# controller_rev4_2b.net
KiCad netlist of a schematic drawn in EAGLE
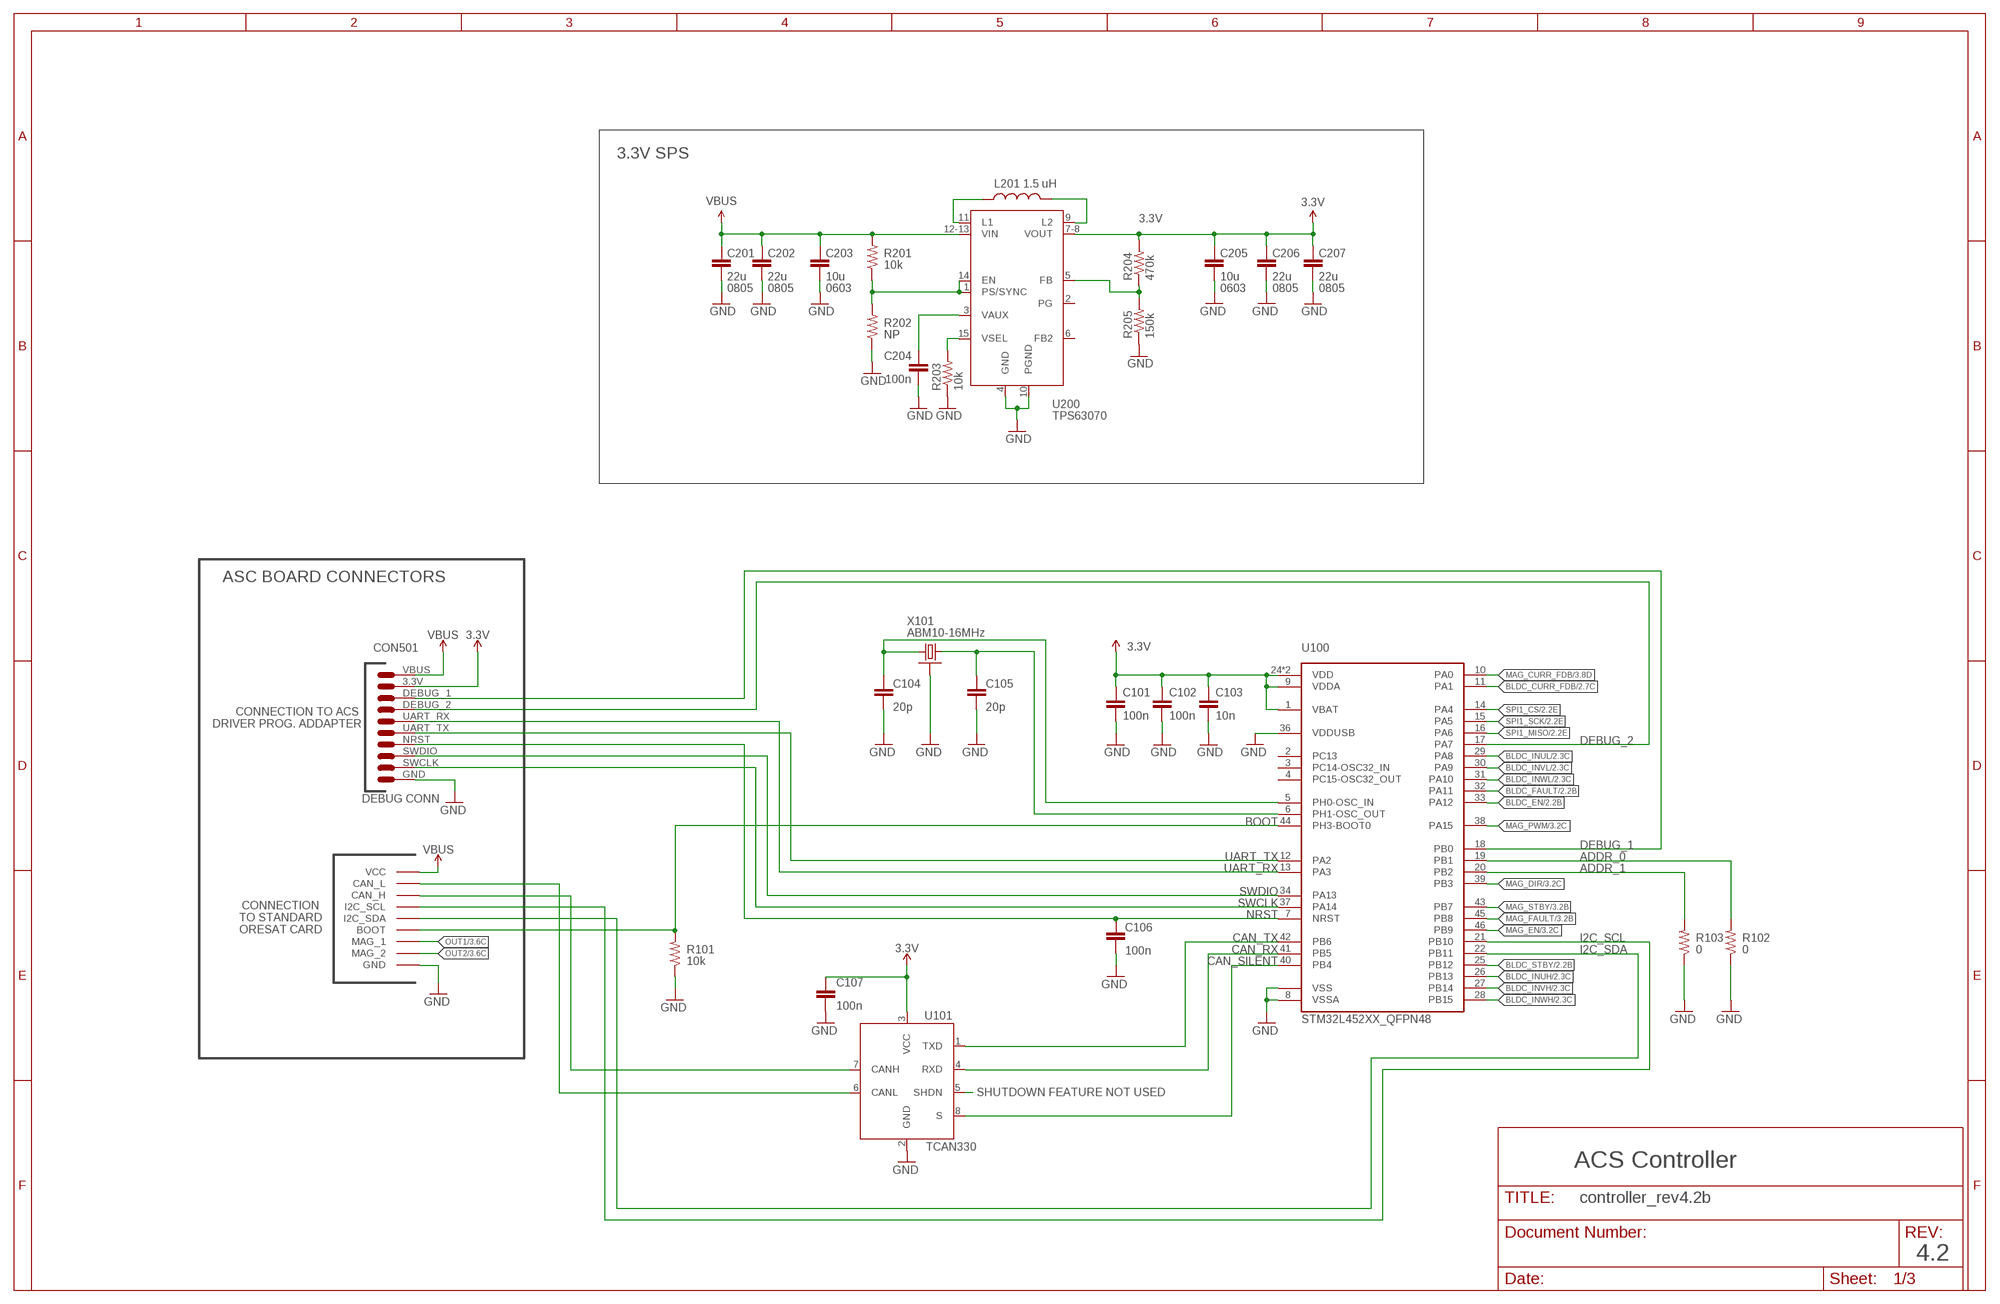
[diagram p0: schematic, sheet 1]
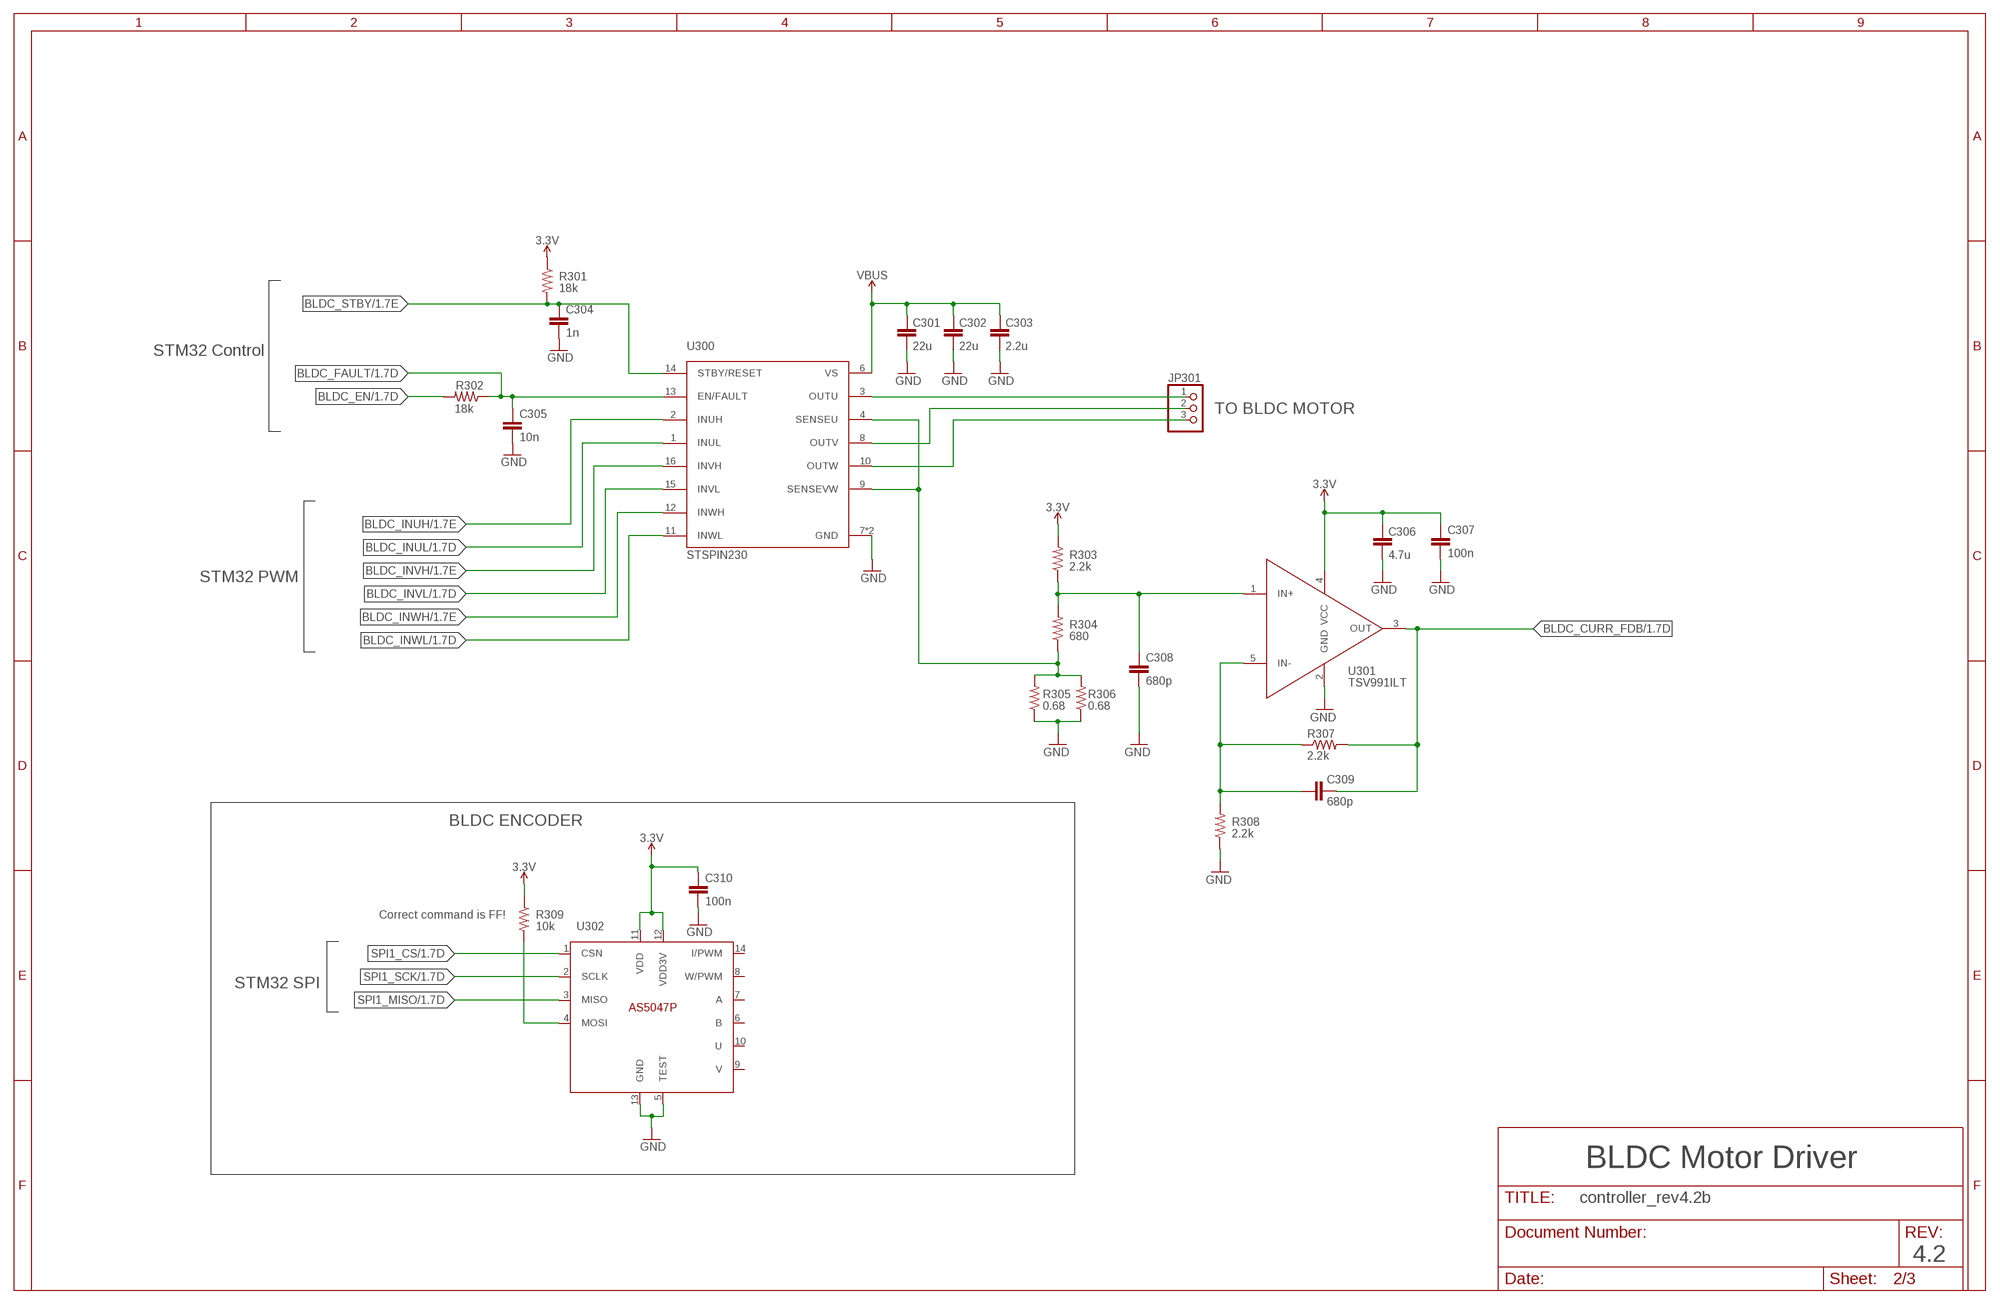
[diagram p1: schematic, sheet 2]
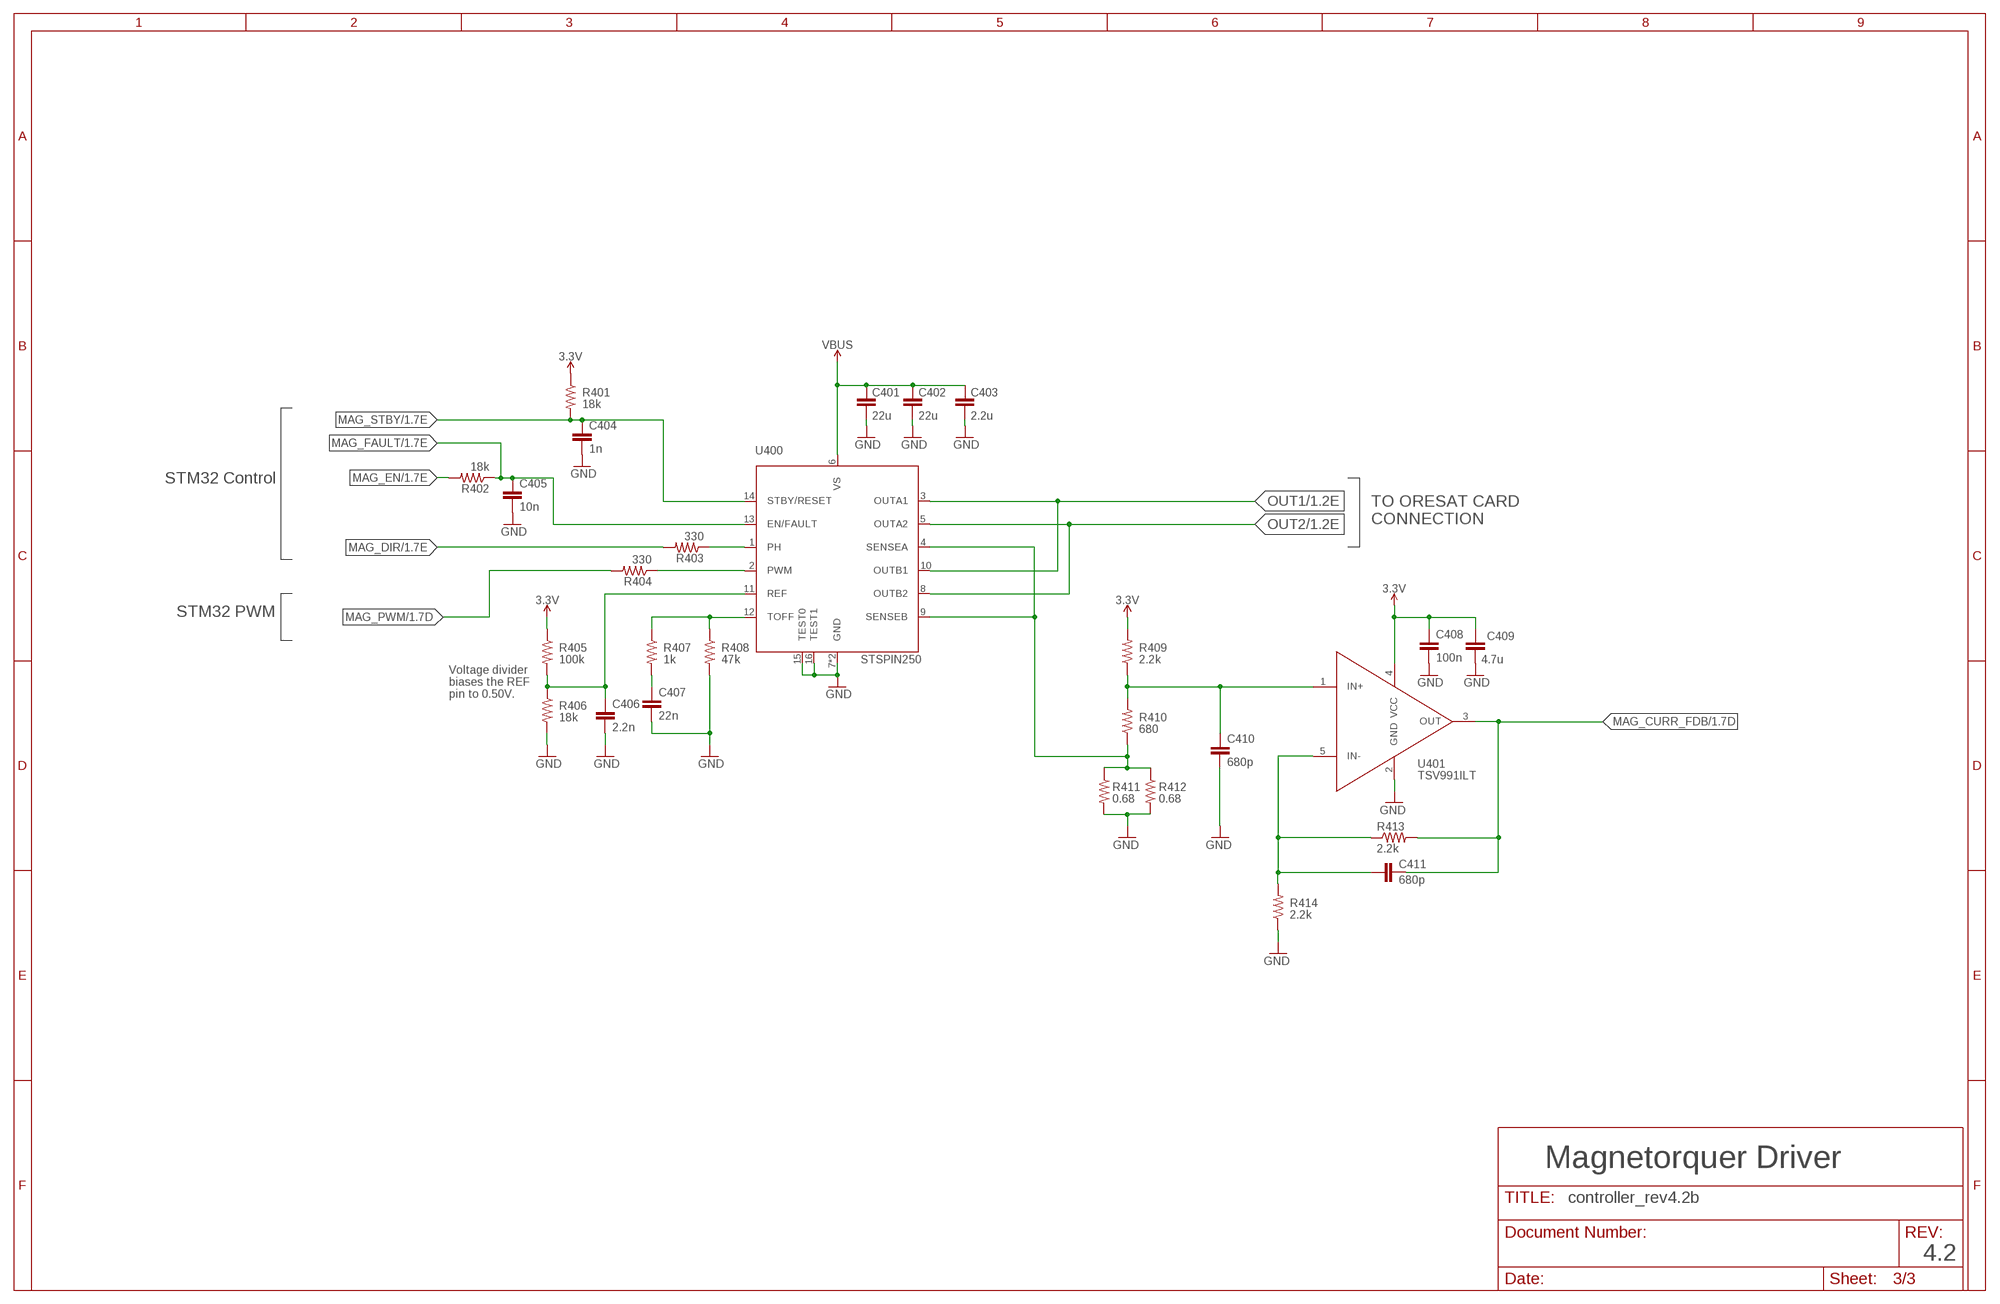
[diagram p2: schematic, sheet 3]

(export (version "E")
  (design (tool "Eeschema 10.0.6"))
  (components
    (comp (ref "C401")
      (value "22u")
      (footprint "eagle-import:.0603-B-NOSILK")
      (fields (field (name "MFR") "Samsung") (field (name "MPN") "CL05B104KO5NNNC"))
      (libsource (lib "eagle-import") (part "C-EU0603-B-NOSILK"))
    )
    (comp (ref "C402")
      (value "22u")
      (footprint "eagle-import:.0603-B-NOSILK")
      (fields (field (name "MFR") "Samsung") (field (name "MPN") "CL05B104KO5NNNC"))
      (libsource (lib "eagle-import") (part "C-EU0603-B-NOSILK"))
    )
    (comp (ref "C403")
      (value "2.2u")
      (footprint "eagle-import:.0603-B-NOSILK")
      (fields (field (name "MFR") "Samsung") (field (name "MPN") "CL05B104KO5NNNC"))
      (libsource (lib "eagle-import") (part "C-EU0603-B-NOSILK"))
    )
    (comp (ref "C404")
      (value "1n")
      (footprint "eagle-import:.0402-B-NOSILK")
      (fields (field (name "MFR") "Samsung") (field (name "MPN") "CL05B104KO5NNNC"))
      (libsource (lib "eagle-import") (part "rcl_custom_C-EU0402-B-NOSILK"))
    )
    (comp (ref "C405")
      (value "10n")
      (footprint "eagle-import:.0402-B-NOSILK")
      (fields (field (name "MFR") "Samsung") (field (name "MPN") "CL05B104KO5NNNC"))
      (libsource (lib "eagle-import") (part "rcl_custom_C-EU0402-B-NOSILK"))
    )
    (comp (ref "C406")
      (value "2.2n")
      (footprint "eagle-import:.0402-B-NOSILK")
      (fields (field (name "MFR") "Samsung") (field (name "MPN") "CL05B104KO5NNNC"))
      (libsource (lib "eagle-import") (part "rcl_custom_C-EU0402-B-NOSILK"))
    )
    (comp (ref "C407")
      (value "22n")
      (footprint "eagle-import:.0402-B-NOSILK")
      (fields (field (name "MFR") "Samsung") (field (name "MPN") "CL05B104KO5NNNC"))
      (libsource (lib "eagle-import") (part "rcl_custom_C-EU0402-B-NOSILK"))
    )
    (comp (ref "C408")
      (value "100n")
      (footprint "eagle-import:.0402-B-NOSILK")
      (fields (field (name "MFR") "Samsung") (field (name "MPN") "CL05B104KO5NNNC"))
      (libsource (lib "eagle-import") (part "rcl_custom_C-EU0402-B-NOSILK"))
    )
    (comp (ref "C409")
      (value "4.7u")
      (footprint "eagle-import:.0603-B-NOSILK")
      (fields (field (name "MFR") "Samsung") (field (name "MPN") "CL05B104KO5NNNC"))
      (libsource (lib "eagle-import") (part "C-EU0603-B-NOSILK"))
    )
    (comp (ref "C410")
      (value "680p")
      (footprint "eagle-import:.0402-B-NOSILK")
      (fields (field (name "MFR") "Samsung") (field (name "MPN") "CL05B104KO5NNNC"))
      (libsource (lib "eagle-import") (part "rcl_custom_C-EU0402-B-NOSILK"))
    )
    (comp (ref "C411")
      (value "680p")
      (footprint "eagle-import:.0402-B-NOSILK")
      (fields (field (name "MFR") "Samsung") (field (name "MPN") "CL05B104KO5NNNC"))
      (libsource (lib "eagle-import") (part "rcl_custom_C-EU0402-B-NOSILK"))
    )
    (comp (ref "R401")
      (value "18k")
      (footprint "eagle-import:.0402-B-NOSILK")
      (fields (field (name "MFR") "Samsung") (field (name "MPN") "RC1005F6653CS"))
      (libsource (lib "eagle-import") (part "rcl_custom_R-US_0402-B-NOSILK"))
    )
    (comp (ref "R402")
      (value "18k")
      (footprint "eagle-import:.0402-B-NOSILK")
      (fields (field (name "MFR") "Samsung") (field (name "MPN") "RC1005F6653CS"))
      (libsource (lib "eagle-import") (part "rcl_custom_R-US_0402-B-NOSILK"))
    )
    (comp (ref "R403")
      (value "330")
      (footprint "eagle-import:.0402-B-NOSILK")
      (fields (field (name "MFR") "Samsung") (field (name "MPN") "RC1005F6653CS"))
      (libsource (lib "eagle-import") (part "rcl_custom_R-US_0402-B-NOSILK"))
    )
    (comp (ref "R404")
      (value "330")
      (footprint "eagle-import:.0402-B-NOSILK")
      (fields (field (name "MFR") "Samsung") (field (name "MPN") "RC1005F6653CS"))
      (libsource (lib "eagle-import") (part "rcl_custom_R-US_0402-B-NOSILK"))
    )
    (comp (ref "R405")
      (value "100k")
      (footprint "eagle-import:.0402-B-NOSILK")
      (fields (field (name "MFR") "Samsung") (field (name "MPN") "RC1005F6653CS"))
      (libsource (lib "eagle-import") (part "rcl_custom_R-US_0402-B-NOSILK"))
    )
    (comp (ref "R406")
      (value "18k")
      (footprint "eagle-import:.0402-B-NOSILK")
      (fields (field (name "MFR") "Samsung") (field (name "MPN") "RC1005F6653CS"))
      (libsource (lib "eagle-import") (part "rcl_custom_R-US_0402-B-NOSILK"))
    )
    (comp (ref "R407")
      (value "1k")
      (footprint "eagle-import:.0402-B-NOSILK")
      (fields (field (name "MFR") "Samsung") (field (name "MPN") "RC1005F6653CS"))
      (libsource (lib "eagle-import") (part "rcl_custom_R-US_0402-B-NOSILK"))
    )
    (comp (ref "R408")
      (value "47k")
      (footprint "eagle-import:.0402-B-NOSILK")
      (fields (field (name "MFR") "Samsung") (field (name "MPN") "RC1005F6653CS"))
      (libsource (lib "eagle-import") (part "rcl_custom_R-US_0402-B-NOSILK"))
    )
    (comp (ref "R409")
      (value "2.2k")
      (footprint "eagle-import:.0402-B-NOSILK")
      (fields (field (name "MFR") "Samsung") (field (name "MPN") "RC1005F6653CS"))
      (libsource (lib "eagle-import") (part "rcl_custom_R-US_0402-B-NOSILK"))
    )
    (comp (ref "R410")
      (value "680")
      (footprint "eagle-import:.0402-B-NOSILK")
      (fields (field (name "MFR") "Samsung") (field (name "MPN") "RC1005F6653CS"))
      (libsource (lib "eagle-import") (part "rcl_custom_R-US_0402-B-NOSILK"))
    )
    (comp (ref "R411")
      (value "0.68")
      (footprint "eagle-import:.0805-B-NOSILK")
      (libsource (lib "eagle-import") (part "R-US_0805-B-NOSILK"))
    )
    (comp (ref "R412")
      (value "0.68")
      (footprint "eagle-import:.0805-B-NOSILK")
      (libsource (lib "eagle-import") (part "R-US_0805-B-NOSILK"))
    )
    (comp (ref "R413")
      (value "2.2k")
      (footprint "eagle-import:.0402-B-NOSILK")
      (fields (field (name "MFR") "Samsung") (field (name "MPN") "RC1005F6653CS"))
      (libsource (lib "eagle-import") (part "rcl_custom_R-US_0402-B-NOSILK"))
    )
    (comp (ref "R414")
      (value "2.2k")
      (footprint "eagle-import:.0402-B-NOSILK")
      (fields (field (name "MFR") "Samsung") (field (name "MPN") "RC1005F6653CS"))
      (libsource (lib "eagle-import") (part "rcl_custom_R-US_0402-B-NOSILK"))
    )
    (comp (ref "U400")
      (value "STSPIN250")
      (footprint "eagle-import:VFQPN")
      (libsource (lib "eagle-import") (part "STSPIN250"))
    )
    (comp (ref "U401")
      (value "TSV991ILT")
      (footprint "eagle-import:SOT23-5")
      (libsource (lib "eagle-import") (part "TSV991ILT"))
    )
    (comp (ref "C301")
      (value "22u")
      (footprint "eagle-import:.0603-B-NOSILK")
      (fields (field (name "MFR") "Samsung") (field (name "MPN") "CL05B104KO5NNNC"))
      (libsource (lib "eagle-import") (part "C-EU0603-B-NOSILK"))
    )
    (comp (ref "C302")
      (value "22u")
      (footprint "eagle-import:.0603-B-NOSILK")
      (fields (field (name "MFR") "Samsung") (field (name "MPN") "CL05B104KO5NNNC"))
      (libsource (lib "eagle-import") (part "C-EU0603-B-NOSILK"))
    )
    (comp (ref "C303")
      (value "2.2u")
      (footprint "eagle-import:.0603-B-NOSILK")
      (fields (field (name "MFR") "Samsung") (field (name "MPN") "CL05B104KO5NNNC"))
      (libsource (lib "eagle-import") (part "C-EU0603-B-NOSILK"))
    )
    (comp (ref "C304")
      (value "1n")
      (footprint "eagle-import:.0402-B-NOSILK")
      (fields (field (name "MFR") "Samsung") (field (name "MPN") "CL05B104KO5NNNC"))
      (libsource (lib "eagle-import") (part "rcl_custom_C-EU0402-B-NOSILK"))
    )
    (comp (ref "C305")
      (value "10n")
      (footprint "eagle-import:.0402-B-NOSILK")
      (fields (field (name "MFR") "Samsung") (field (name "MPN") "CL05B104KO5NNNC"))
      (libsource (lib "eagle-import") (part "rcl_custom_C-EU0402-B-NOSILK"))
    )
    (comp (ref "C306")
      (value "4.7u")
      (footprint "eagle-import:.0603-B-NOSILK")
      (fields (field (name "MFR") "Samsung") (field (name "MPN") "CL05B104KO5NNNC"))
      (libsource (lib "eagle-import") (part "C-EU0603-B-NOSILK"))
    )
    (comp (ref "C307")
      (value "100n")
      (footprint "eagle-import:.0402-B-NOSILK")
      (fields (field (name "MFR") "Samsung") (field (name "MPN") "CL05B104KO5NNNC"))
      (libsource (lib "eagle-import") (part "rcl_custom_C-EU0402-B-NOSILK"))
    )
    (comp (ref "C308")
      (value "680p")
      (footprint "eagle-import:.0402-B-NOSILK")
      (fields (field (name "MFR") "Samsung") (field (name "MPN") "CL05B104KO5NNNC"))
      (libsource (lib "eagle-import") (part "rcl_custom_C-EU0402-B-NOSILK"))
    )
    (comp (ref "C309")
      (value "680p")
      (footprint "eagle-import:.0402-B-NOSILK")
      (fields (field (name "MFR") "Samsung") (field (name "MPN") "CL05B104KO5NNNC"))
      (libsource (lib "eagle-import") (part "rcl_custom_C-EU0402-B-NOSILK"))
    )
    (comp (ref "C310")
      (value "100n")
      (footprint "eagle-import:.0402-B-NOSILK")
      (fields (field (name "MFR") "Samsung") (field (name "MPN") "CL05B104KO5NNNC"))
      (libsource (lib "eagle-import") (part "rcl_custom_C-EU0402-B-NOSILK"))
    )
    (comp (ref "JP301")
      (value "PINHD-1X03_2.00")
      (footprint "eagle-import:1X03M")
      (libsource (lib "eagle-import") (part "PINHD-1X03_2.00"))
    )
    (comp (ref "R301")
      (value "18k")
      (footprint "eagle-import:.0402-B-NOSILK")
      (fields (field (name "MFR") "Samsung") (field (name "MPN") "RC1005F6653CS"))
      (libsource (lib "eagle-import") (part "rcl_custom_R-US_0402-B-NOSILK"))
    )
    (comp (ref "R302")
      (value "18k")
      (footprint "eagle-import:.0402-B-NOSILK")
      (fields (field (name "MFR") "Samsung") (field (name "MPN") "RC1005F6653CS"))
      (libsource (lib "eagle-import") (part "rcl_custom_R-US_0402-B-NOSILK"))
    )
    (comp (ref "R303")
      (value "2.2k")
      (footprint "eagle-import:.0402-B-NOSILK")
      (fields (field (name "MFR") "Samsung") (field (name "MPN") "RC1005F6653CS"))
      (libsource (lib "eagle-import") (part "rcl_custom_R-US_0402-B-NOSILK"))
    )
    (comp (ref "R304")
      (value "680")
      (footprint "eagle-import:.0402-B-NOSILK")
      (fields (field (name "MFR") "Samsung") (field (name "MPN") "RC1005F6653CS"))
      (libsource (lib "eagle-import") (part "rcl_custom_R-US_0402-B-NOSILK"))
    )
    (comp (ref "R305")
      (value "0.68")
      (footprint "eagle-import:.0805-B-NOSILK")
      (libsource (lib "eagle-import") (part "R-US_0805-B-NOSILK"))
    )
    (comp (ref "R306")
      (value "0.68")
      (footprint "eagle-import:.0805-B-NOSILK")
      (libsource (lib "eagle-import") (part "R-US_0805-B-NOSILK"))
    )
    (comp (ref "R307")
      (value "2.2k")
      (footprint "eagle-import:.0402-B-NOSILK")
      (fields (field (name "MFR") "Samsung") (field (name "MPN") "RC1005F6653CS"))
      (libsource (lib "eagle-import") (part "rcl_custom_R-US_0402-B-NOSILK"))
    )
    (comp (ref "R308")
      (value "2.2k")
      (footprint "eagle-import:.0402-B-NOSILK")
      (fields (field (name "MFR") "Samsung") (field (name "MPN") "RC1005F6653CS"))
      (libsource (lib "eagle-import") (part "rcl_custom_R-US_0402-B-NOSILK"))
    )
    (comp (ref "R309")
      (value "10k")
      (footprint "eagle-import:.0402-B-NOSILK")
      (fields (field (name "MFR") "Samsung") (field (name "MPN") "RC1005F6653CS"))
      (libsource (lib "eagle-import") (part "rcl_custom_R-US_0402-B-NOSILK"))
    )
    (comp (ref "U300")
      (value "STSPIN230")
      (footprint "eagle-import:VFQPN")
      (libsource (lib "eagle-import") (part "STSPIN230"))
    )
    (comp (ref "U301")
      (value "TSV991ILT")
      (footprint "eagle-import:SOT23-5")
      (libsource (lib "eagle-import") (part "TSV991ILT"))
    )
    (comp (ref "U302")
      (value "AS5047P")
      (footprint "eagle-import:TSSOP14")
      (libsource (lib "eagle-import") (part "AS5047P"))
    )
    (comp (ref "C101")
      (value "100n")
      (footprint "eagle-import:.0402-B-NOSILK")
      (fields (field (name "MFR") "Samsung") (field (name "MPN") "CL05B104KO5NNNC"))
      (libsource (lib "eagle-import") (part "rcl_custom_C-EU0402-B-NOSILK"))
    )
    (comp (ref "C102")
      (value "100n")
      (footprint "eagle-import:.0402-B-NOSILK")
      (fields (field (name "MFR") "Samsung") (field (name "MPN") "CL05B104KO5NNNC"))
      (libsource (lib "eagle-import") (part "rcl_custom_C-EU0402-B-NOSILK"))
    )
    (comp (ref "C103")
      (value "10n")
      (footprint "eagle-import:.0402-B-NOSILK")
      (fields (field (name "MFR") "Samsung") (field (name "MPN") "CL05B104KO5NNNC"))
      (libsource (lib "eagle-import") (part "rcl_custom_C-EU0402-B-NOSILK"))
    )
    (comp (ref "C104")
      (value "20p")
      (footprint "eagle-import:.0402-B-NOSILK")
      (fields (field (name "MFR") "Samsung") (field (name "MPN") "CL05C200JB51PNC"))
      (libsource (lib "eagle-import") (part "rcl_custom_C-EU0402-B-NOSILK"))
    )
    (comp (ref "C105")
      (value "20p")
      (footprint "eagle-import:.0402-B-NOSILK")
      (fields (field (name "MFR") "Samsung") (field (name "MPN") "CL05C200JB51PNC"))
      (libsource (lib "eagle-import") (part "rcl_custom_C-EU0402-B-NOSILK"))
    )
    (comp (ref "C106")
      (value "100n")
      (footprint "eagle-import:.0402-B-NOSILK")
      (fields (field (name "MFR") "Samsung") (field (name "MPN") "CL05C200JB51PNC"))
      (libsource (lib "eagle-import") (part "rcl_custom_C-EU0402-B-NOSILK"))
    )
    (comp (ref "C107")
      (value "100n")
      (footprint "eagle-import:.0402-B-NOSILK")
      (fields (field (name "MFR") "Samsung") (field (name "MPN") "CL05B104KO5NNNC"))
      (libsource (lib "eagle-import") (part "rcl_custom_C-EU0402-B-NOSILK"))
    )
    (comp (ref "C201")
      (value "22u")
      (footprint "eagle-import:.0805-B-NOSILK")
      (libsource (lib "eagle-import") (part "C-EU0805-B-NOSILK"))
    )
    (comp (ref "C202")
      (value "22u")
      (footprint "eagle-import:.0805-B-NOSILK")
      (libsource (lib "eagle-import") (part "C-EU0805-B-NOSILK"))
    )
    (comp (ref "C203")
      (value "10u")
      (footprint "eagle-import:.0603-B-NOSILK")
      (fields (field (name "MFR") "Samsung") (field (name "MPN") "CL05B104KO5NNNC"))
      (libsource (lib "eagle-import") (part "C-EU0603-B-NOSILK"))
    )
    (comp (ref "C204")
      (value "100n")
      (footprint "eagle-import:.0402-B-NOSILK")
      (fields (field (name "MFR") "Samsung") (field (name "MPN") "CL05B104KO5NNNC"))
      (libsource (lib "eagle-import") (part "rcl_custom_C-EU0402-B-NOSILK"))
    )
    (comp (ref "C205")
      (value "10u")
      (footprint "eagle-import:.0603-B-NOSILK")
      (fields (field (name "MFR") "Samsung") (field (name "MPN") "CL05B104KO5NNNC"))
      (libsource (lib "eagle-import") (part "C-EU0603-B-NOSILK"))
    )
    (comp (ref "C206")
      (value "22u")
      (footprint "eagle-import:.0805-B-NOSILK")
      (libsource (lib "eagle-import") (part "C-EU0805-B-NOSILK"))
    )
    (comp (ref "C207")
      (value "22u")
      (footprint "eagle-import:.0805-B-NOSILK")
      (libsource (lib "eagle-import") (part "C-EU0805-B-NOSILK"))
    )
    (comp (ref "C501")
      (value "DEBUG_CON")
      (footprint "eagle-import:DEBUG_CON")
      (libsource (lib "eagle-import") (part "DEBUG_CON"))
    )
    (comp (ref "L201")
      (value "1.5 uH")
      (footprint "eagle-import:L-COILCRAFT-XFL4020")
      (fields (field (name "MFR") "Coilcraft") (field (name "MPN") "XFL4020-152ME"))
      (libsource (lib "eagle-import") (part "L-COILCRAFT-XFL4020"))
    )
    (comp (ref "R101")
      (value "10k")
      (footprint "eagle-import:.0402-B-NOSILK")
      (fields (field (name "MFR") "Samsung") (field (name "MPN") "RC1005F6653CS"))
      (libsource (lib "eagle-import") (part "rcl_custom_R-US_0402-B-NOSILK"))
    )
    (comp (ref "R102")
      (value "0")
      (footprint "eagle-import:.0402-B-NOSILK")
      (fields (field (name "MFR") "Samsung") (field (name "MPN") "RC1005F6653CS"))
      (libsource (lib "eagle-import") (part "rcl_custom_R-US_0402-B-NOSILK"))
    )
    (comp (ref "R103")
      (value "0")
      (footprint "eagle-import:.0402-B-NOSILK")
      (fields (field (name "MFR") "Samsung") (field (name "MPN") "RC1005F6653CS"))
      (libsource (lib "eagle-import") (part "rcl_custom_R-US_0402-B-NOSILK"))
    )
    (comp (ref "R201")
      (value "10k")
      (footprint "eagle-import:.0402-B-NOSILK")
      (fields (field (name "MFR") "Samsung") (field (name "MPN") "RC1005F6653CS"))
      (libsource (lib "eagle-import") (part "rcl_custom_R-US_0402-B-NOSILK"))
    )
    (comp (ref "R202")
      (value "NP")
      (footprint "eagle-import:.0402-B-NOSILK")
      (fields (field (name "MFR") "Samsung") (field (name "MPN") "RC1005F6653CS"))
      (libsource (lib "eagle-import") (part "rcl_custom_R-US_0402-B-NOSILK"))
    )
    (comp (ref "R203")
      (value "10k")
      (footprint "eagle-import:.0402-B-NOSILK")
      (fields (field (name "MFR") "Samsung") (field (name "MPN") "RC1005F6653CS"))
      (libsource (lib "eagle-import") (part "rcl_custom_R-US_0402-B-NOSILK"))
    )
    (comp (ref "R204")
      (value "470k")
      (footprint "eagle-import:.0402-B-NOSILK")
      (fields (field (name "MFR") "Samsung") (field (name "MPN") "RC1005F6653CS"))
      (libsource (lib "eagle-import") (part "rcl_custom_R-US_0402-B-NOSILK"))
    )
    (comp (ref "R205")
      (value "150k")
      (footprint "eagle-import:.0402-B-NOSILK")
      (fields (field (name "MFR") "Samsung") (field (name "MPN") "RC1005F6653CS"))
      (libsource (lib "eagle-import") (part "rcl_custom_R-US_0402-B-NOSILK"))
    )
    (comp (ref "U$2")
      (value "MEZZANINE_1")
      (footprint "eagle-import:MEZZANINE_1")
      (libsource (lib "eagle-import") (part "MEZZANINE_1"))
    )
    (comp (ref "U100")
      (value "STM32L452XX_QFPN48")
      (footprint "eagle-import:QFPN-48")
      (libsource (lib "eagle-import") (part "STM32L452XX_QFPN48"))
    )
    (comp (ref "U101")
      (value "TCAN330")
      (footprint "eagle-import:SOT23-8_TI-DCN")
      (fields (field (name "MFR") "Texas Instruments") (field (name "MPN") "TCAN330GDCNT"))
      (libsource (lib "eagle-import") (part "TCAN330"))
    )
    (comp (ref "U200")
      (value "TPS63070")
      (footprint "eagle-import:TPS63070X")
      (fields (field (name "MFR") "TI"))
      (libsource (lib "eagle-import") (part "TPS63070X"))
    )
    (comp (ref "X101")
      (value "ABM10-16MHz")
      (footprint "eagle-import:CRYSTAL_2.5X2")
      (fields (field (name "MFR") "ECS Inc.") (field (name "MPN") "ECS-160-10-36Q-ES-TR"))
      (libsource (lib "eagle-import") (part "CRYSTAL-WITH-GND"))
    )
  )
  (nets
    (net (code "1") (name "3.3V") (class "Default")
      (node (ref "C101") (pin "1") (pinfunction "1_1") (pintype "passive"))
      (node (ref "C102") (pin "1") (pinfunction "1_1") (pintype "passive"))
      (node (ref "C103") (pin "1") (pinfunction "1_1") (pintype "passive"))
      (node (ref "C107") (pin "1") (pinfunction "1_1") (pintype "passive"))
      (node (ref "C205") (pin "1") (pinfunction "1_1") (pintype "passive"))
      (node (ref "C206") (pin "1") (pinfunction "1_1") (pintype "passive"))
      (node (ref "C207") (pin "1") (pinfunction "1_1") (pintype "passive"))
      (node (ref "C306") (pin "1") (pinfunction "1_1") (pintype "passive"))
      (node (ref "C307") (pin "1") (pinfunction "1_1") (pintype "passive"))
      (node (ref "C310") (pin "1") (pinfunction "1_1") (pintype "passive"))
      (node (ref "C408") (pin "1") (pinfunction "1_1") (pintype "passive"))
      (node (ref "C409") (pin "1") (pinfunction "1_1") (pintype "passive"))
      (node (ref "C501") (pin "3.3V") (pinfunction "2_3.3V") (pintype "bidirectional"))
      (node (ref "R204") (pin "2") (pinfunction "2_2") (pintype "passive"))
      (node (ref "R301") (pin "1") (pinfunction "1_1") (pintype "passive"))
      (node (ref "R303") (pin "2") (pinfunction "2_2") (pintype "passive"))
      (node (ref "R309") (pin "1") (pinfunction "1_1") (pintype "passive"))
      (node (ref "R401") (pin "1") (pinfunction "1_1") (pintype "passive"))
      (node (ref "R405") (pin "1") (pinfunction "1_1") (pintype "passive"))
      (node (ref "R409") (pin "2") (pinfunction "2_2") (pintype "passive"))
      (node (ref "U100") (pin "1") (pinfunction "VBAT_1") (pintype "bidirectional"))
      (node (ref "U100") (pin "24") (pinfunction "VDD_24") (pintype "bidirectional"))
      (node (ref "U100") (pin "48") (pinfunction "VDD_48") (pintype "bidirectional"))
      (node (ref "U100") (pin "9") (pinfunction "VDDA_9") (pintype "bidirectional"))
      (node (ref "U101") (pin "3") (pinfunction "VCC_3") (pintype "power_in"))
      (node (ref "U200") (pin "7-8") (pinfunction "VOUT_7-8") (pintype "power_in"))
      (node (ref "U301") (pin "4") (pinfunction "VCC_4") (pintype "bidirectional"))
      (node (ref "U302") (pin "11") (pinfunction "VDD_11") (pintype "power_in"))
      (node (ref "U302") (pin "12") (pinfunction "VDD3V_12") (pintype "power_in"))
      (node (ref "U401") (pin "4") (pinfunction "VCC_4") (pintype "bidirectional"))
    )
    (net (code "2") (name "ADDR_0") (class "Default")
      (node (ref "R102") (pin "2") (pinfunction "2_2") (pintype "passive"))
      (node (ref "U100") (pin "19") (pinfunction "PB1_19") (pintype "bidirectional"))
    )
    (net (code "3") (name "ADDR_1") (class "Default")
      (node (ref "R103") (pin "2") (pinfunction "2_2") (pintype "passive"))
      (node (ref "U100") (pin "20") (pinfunction "PB2_20") (pintype "bidirectional"))
    )
    (net (code "4") (name "BLDC_CURR_FDB") (class "Default")
      (node (ref "C309") (pin "1") (pinfunction "1_1") (pintype "passive"))
      (node (ref "R307") (pin "2") (pinfunction "2_2") (pintype "passive"))
      (node (ref "U100") (pin "11") (pinfunction "PA1_11") (pintype "bidirectional"))
      (node (ref "U301") (pin "3") (pinfunction "OUT_3") (pintype "bidirectional"))
    )
    (net (code "5") (name "BLDC_EN") (class "Default")
      (node (ref "R302") (pin "2") (pinfunction "2_2") (pintype "passive"))
      (node (ref "U100") (pin "33") (pinfunction "PA12_33") (pintype "bidirectional"))
    )
    (net (code "6") (name "BLDC_FAULT") (class "Default")
      (node (ref "C305") (pin "1") (pinfunction "1_1") (pintype "passive"))
      (node (ref "R302") (pin "1") (pinfunction "1_1") (pintype "passive"))
      (node (ref "U100") (pin "32") (pinfunction "PA11_32") (pintype "bidirectional"))
      (node (ref "U300") (pin "13") (pinfunction "EN/FAULT_13") (pintype "bidirectional"))
    )
    (net (code "7") (name "BLDC_INUH") (class "Default")
      (node (ref "U100") (pin "26") (pinfunction "PB13_26") (pintype "bidirectional"))
      (node (ref "U300") (pin "2") (pinfunction "INUH_2") (pintype "input"))
    )
    (net (code "8") (name "BLDC_INUL") (class "Default")
      (node (ref "U100") (pin "29") (pinfunction "PA8_29") (pintype "bidirectional"))
      (node (ref "U300") (pin "1") (pinfunction "INUL_1") (pintype "input"))
    )
    (net (code "9") (name "BLDC_INVH") (class "Default")
      (node (ref "U100") (pin "27") (pinfunction "PB14_27") (pintype "bidirectional"))
      (node (ref "U300") (pin "16") (pinfunction "INVH_16") (pintype "input"))
    )
    (net (code "10") (name "BLDC_INVL") (class "Default")
      (node (ref "U100") (pin "30") (pinfunction "PA9_30") (pintype "bidirectional"))
      (node (ref "U300") (pin "15") (pinfunction "INVL_15") (pintype "input"))
    )
    (net (code "11") (name "BLDC_INWH") (class "Default")
      (node (ref "U100") (pin "28") (pinfunction "PB15_28") (pintype "bidirectional"))
      (node (ref "U300") (pin "12") (pinfunction "INWH_12") (pintype "input"))
    )
    (net (code "12") (name "BLDC_INWL") (class "Default")
      (node (ref "U100") (pin "31") (pinfunction "PA10_31") (pintype "bidirectional"))
      (node (ref "U300") (pin "11") (pinfunction "INWL_11") (pintype "input"))
    )
    (net (code "13") (name "BLDC_STBY") (class "Default")
      (node (ref "C304") (pin "1") (pinfunction "1_1") (pintype "passive"))
      (node (ref "R301") (pin "2") (pinfunction "2_2") (pintype "passive"))
      (node (ref "U100") (pin "25") (pinfunction "PB12_25") (pintype "bidirectional"))
      (node (ref "U300") (pin "14") (pinfunction "STBY/RESET_14") (pintype "input"))
    )
    (net (code "14") (name "BOOT") (class "Default")
      (node (ref "R101") (pin "2") (pinfunction "2_2") (pintype "passive"))
      (node (ref "U$2") (pin "P$22") (pinfunction "BOOT_P$22") (pintype "bidirectional"))
      (node (ref "U$2") (pin "P$9") (pinfunction "BOOT_P$9") (pintype "bidirectional"))
      (node (ref "U100") (pin "44") (pinfunction "PH3-BOOT0_44") (pintype "bidirectional"))
    )
    (net (code "15") (name "CAN_RX") (class "Default")
      (node (ref "U100") (pin "41") (pinfunction "PB5_41") (pintype "bidirectional"))
      (node (ref "U101") (pin "4") (pinfunction "RXD_4") (pintype "output"))
    )
    (net (code "16") (name "CAN_SILENT") (class "Default")
      (node (ref "U100") (pin "40") (pinfunction "PB4_40") (pintype "bidirectional"))
      (node (ref "U101") (pin "8") (pinfunction "S_8") (pintype "input"))
    )
    (net (code "17") (name "CAN_TX") (class "Default")
      (node (ref "U100") (pin "42") (pinfunction "PB6_42") (pintype "bidirectional"))
      (node (ref "U101") (pin "1") (pinfunction "TXD_1") (pintype "input"))
    )
    (net (code "18") (name "DEBUG_1") (class "Default")
      (node (ref "C501") (pin "DEBUG_1") (pinfunction "3_DEBUG_1") (pintype "bidirectional"))
      (node (ref "U100") (pin "18") (pinfunction "PB0_18") (pintype "bidirectional"))
    )
    (net (code "19") (name "DEBUG_2") (class "Default")
      (node (ref "C501") (pin "DEBUG_2") (pinfunction "4_DEBUG_2") (pintype "bidirectional"))
      (node (ref "U100") (pin "17") (pinfunction "PA7_17") (pintype "bidirectional"))
    )
    (net (code "20") (name "GND") (class "Default")
      (node (ref "C101") (pin "2") (pinfunction "2_2") (pintype "passive"))
      (node (ref "C102") (pin "2") (pinfunction "2_2") (pintype "passive"))
      (node (ref "C103") (pin "2") (pinfunction "2_2") (pintype "passive"))
      (node (ref "C104") (pin "2") (pinfunction "2_2") (pintype "passive"))
      (node (ref "C105") (pin "2") (pinfunction "2_2") (pintype "passive"))
      (node (ref "C106") (pin "2") (pinfunction "2_2") (pintype "passive"))
      (node (ref "C107") (pin "2") (pinfunction "2_2") (pintype "passive"))
      (node (ref "C201") (pin "2") (pinfunction "2_2") (pintype "passive"))
      (node (ref "C202") (pin "2") (pinfunction "2_2") (pintype "passive"))
      (node (ref "C203") (pin "2") (pinfunction "2_2") (pintype "passive"))
      (node (ref "C204") (pin "2") (pinfunction "2_2") (pintype "passive"))
      (node (ref "C205") (pin "2") (pinfunction "2_2") (pintype "passive"))
      (node (ref "C206") (pin "2") (pinfunction "2_2") (pintype "passive"))
      (node (ref "C207") (pin "2") (pinfunction "2_2") (pintype "passive"))
      (node (ref "C301") (pin "2") (pinfunction "2_2") (pintype "passive"))
      (node (ref "C302") (pin "2") (pinfunction "2_2") (pintype "passive"))
      (node (ref "C303") (pin "2") (pinfunction "2_2") (pintype "passive"))
      (node (ref "C304") (pin "2") (pinfunction "2_2") (pintype "passive"))
      (node (ref "C305") (pin "2") (pinfunction "2_2") (pintype "passive"))
      (node (ref "C306") (pin "2") (pinfunction "2_2") (pintype "passive"))
      (node (ref "C307") (pin "2") (pinfunction "2_2") (pintype "passive"))
      (node (ref "C308") (pin "2") (pinfunction "2_2") (pintype "passive"))
      (node (ref "C310") (pin "2") (pinfunction "2_2") (pintype "passive"))
      (node (ref "C401") (pin "2") (pinfunction "2_2") (pintype "passive"))
      (node (ref "C402") (pin "2") (pinfunction "2_2") (pintype "passive"))
      (node (ref "C403") (pin "2") (pinfunction "2_2") (pintype "passive"))
      (node (ref "C404") (pin "2") (pinfunction "2_2") (pintype "passive"))
      (node (ref "C405") (pin "2") (pinfunction "2_2") (pintype "passive"))
      (node (ref "C406") (pin "2") (pinfunction "2_2") (pintype "passive"))
      (node (ref "C407") (pin "2") (pinfunction "2_2") (pintype "passive"))
      (node (ref "C408") (pin "2") (pinfunction "2_2") (pintype "passive"))
      (node (ref "C409") (pin "2") (pinfunction "2_2") (pintype "passive"))
      (node (ref "C410") (pin "2") (pinfunction "2_2") (pintype "passive"))
      (node (ref "C501") (pin "GND") (pinfunction "10_GND") (pintype "bidirectional"))
      (node (ref "R101") (pin "1") (pinfunction "1_1") (pintype "passive"))
      (node (ref "R102") (pin "1") (pinfunction "1_1") (pintype "passive"))
      (node (ref "R103") (pin "1") (pinfunction "1_1") (pintype "passive"))
      (node (ref "R202") (pin "1") (pinfunction "1_1") (pintype "passive"))
      (node (ref "R203") (pin "1") (pinfunction "1_1") (pintype "passive"))
      (node (ref "R205") (pin "1") (pinfunction "1_1") (pintype "passive"))
      (node (ref "R305") (pin "1") (pinfunction "1_1") (pintype "passive"))
      (node (ref "R306") (pin "1") (pinfunction "1_1") (pintype "passive"))
      (node (ref "R308") (pin "1") (pinfunction "1_1") (pintype "passive"))
      (node (ref "R406") (pin "2") (pinfunction "2_2") (pintype "passive"))
      (node (ref "R408") (pin "2") (pinfunction "2_2") (pintype "passive"))
      (node (ref "R411") (pin "2") (pinfunction "2_2") (pintype "passive"))
      (node (ref "R412") (pin "2") (pinfunction "2_2") (pintype "passive"))
      (node (ref "R414") (pin "1") (pinfunction "1_1") (pintype "passive"))
      (node (ref "U$2") (pin "P$1") (pinfunction "GND_P$1") (pintype "bidirectional"))
      (node (ref "U$2") (pin "P$14") (pinfunction "GND_P$14") (pintype "bidirectional"))
      (node (ref "U$2") (pin "P$15") (pinfunction "GND_P$15") (pintype "bidirectional"))
      (node (ref "U$2") (pin "P$16") (pinfunction "GND_P$16") (pintype "bidirectional"))
      (node (ref "U$2") (pin "P$17") (pinfunction "GND_P$17") (pintype "bidirectional"))
      (node (ref "U$2") (pin "P$2") (pinfunction "GND_P$2") (pintype "bidirectional"))
      (node (ref "U$2") (pin "P$29") (pinfunction "GND_P$29") (pintype "bidirectional"))
      (node (ref "U$2") (pin "P$30") (pinfunction "GND_P$30") (pintype "bidirectional"))
      (node (ref "U100") (pin "23") (pinfunction "VSS_23") (pintype "bidirectional"))
      (node (ref "U100") (pin "35") (pinfunction "VSS_35") (pintype "bidirectional"))
      (node (ref "U100") (pin "36") (pinfunction "VDDUSB_36") (pintype "bidirectional"))
      (node (ref "U100") (pin "47") (pinfunction "VSS_47") (pintype "bidirectional"))
      (node (ref "U100") (pin "8") (pinfunction "VSSA_8") (pintype "bidirectional"))
      (node (ref "U100") (pin "EPAD") (pinfunction "VSS_EPAD") (pintype "bidirectional"))
      (node (ref "U101") (pin "2") (pinfunction "GND_2") (pintype "power_in"))
      (node (ref "U200") (pin "10") (pinfunction "PGND_10") (pintype "power_in"))
      (node (ref "U200") (pin "4") (pinfunction "GND_4") (pintype "power_in"))
      (node (ref "U300") (pin "7") (pinfunction "GND_7") (pintype "power_in"))
      (node (ref "U300") (pin "EPAD") (pinfunction "GND_EPAD") (pintype "power_in"))
      (node (ref "U301") (pin "2") (pinfunction "GND_2") (pintype "bidirectional"))
      (node (ref "U302") (pin "13") (pinfunction "GND_13") (pintype "power_in"))
      (node (ref "U302") (pin "5") (pinfunction "TEST_5") (pintype "power_in"))
      (node (ref "U400") (pin "15") (pinfunction "TEST0_15") (pintype "bidirectional"))
      (node (ref "U400") (pin "16") (pinfunction "TEST1_16") (pintype "bidirectional"))
      (node (ref "U400") (pin "7") (pinfunction "GND_7") (pintype "power_in"))
      (node (ref "U400") (pin "EPAD") (pinfunction "GND_EPAD") (pintype "power_in"))
      (node (ref "U401") (pin "2") (pinfunction "GND_2") (pintype "bidirectional"))
      (node (ref "X101") (pin "2") (pinfunction "SHIELD_2") (pintype "power_in"))
      (node (ref "X101") (pin "4") (pinfunction "SHIELD_4") (pintype "power_in"))
    )
    (net (code "21") (name "I2C_SCL") (class "Default")
      (node (ref "U$2") (pin "P$24") (pinfunction "I2C_SCL_P$24") (pintype "bidirectional"))
      (node (ref "U$2") (pin "P$7") (pinfunction "I2C_SCL_P$7") (pintype "bidirectional"))
      (node (ref "U100") (pin "21") (pinfunction "PB10_21") (pintype "bidirectional"))
    )
    (net (code "22") (name "I2C_SDA") (class "Default")
      (node (ref "U$2") (pin "P$23") (pinfunction "I2C_SDA_P$23") (pintype "bidirectional"))
      (node (ref "U$2") (pin "P$8") (pinfunction "I2C_SDA_P$8") (pintype "bidirectional"))
      (node (ref "U100") (pin "22") (pinfunction "PB11_22") (pintype "bidirectional"))
    )
    (net (code "23") (name "MAG_CURR_FDB") (class "Default")
      (node (ref "C411") (pin "1") (pinfunction "1_1") (pintype "passive"))
      (node (ref "R413") (pin "2") (pinfunction "2_2") (pintype "passive"))
      (node (ref "U100") (pin "10") (pinfunction "PA0_10") (pintype "bidirectional"))
      (node (ref "U401") (pin "3") (pinfunction "OUT_3") (pintype "bidirectional"))
    )
    (net (code "24") (name "MAG_DIR") (class "Default")
      (node (ref "R403") (pin "2") (pinfunction "2_2") (pintype "passive"))
      (node (ref "U100") (pin "39") (pinfunction "PB3_39") (pintype "bidirectional"))
    )
    (net (code "25") (name "MAG_EN") (class "Default")
      (node (ref "R402") (pin "2") (pinfunction "2_2") (pintype "passive"))
      (node (ref "U100") (pin "46") (pinfunction "PB9_46") (pintype "bidirectional"))
    )
    (net (code "26") (name "MAG_FAULT") (class "Default")
      (node (ref "C405") (pin "1") (pinfunction "1_1") (pintype "passive"))
      (node (ref "R402") (pin "1") (pinfunction "1_1") (pintype "passive"))
      (node (ref "U100") (pin "45") (pinfunction "PB8_45") (pintype "bidirectional"))
      (node (ref "U400") (pin "13") (pinfunction "EN/FAULT_13") (pintype "bidirectional"))
    )
    (net (code "27") (name "MAG_PWM") (class "Default")
      (node (ref "R404") (pin "2") (pinfunction "2_2") (pintype "passive"))
      (node (ref "U100") (pin "38") (pinfunction "PA15_38") (pintype "bidirectional"))
    )
    (net (code "28") (name "MAG_STBY") (class "Default")
      (node (ref "C404") (pin "1") (pinfunction "1_1") (pintype "passive"))
      (node (ref "R401") (pin "2") (pinfunction "2_2") (pintype "passive"))
      (node (ref "U100") (pin "43") (pinfunction "PB7_43") (pintype "bidirectional"))
      (node (ref "U400") (pin "14") (pinfunction "STBY/RESET_14") (pintype "bidirectional"))
    )
    (net (code "29") (name "NRST") (class "Default")
      (node (ref "C106") (pin "1") (pinfunction "1_1") (pintype "passive"))
      (node (ref "C501") (pin "NRST") (pinfunction "7_NRST") (pintype "bidirectional"))
      (node (ref "U100") (pin "7") (pinfunction "NRST_7") (pintype "bidirectional"))
    )
    (net (code "30") (name "Net-(C407-Pad1)") (class "Default")
      (node (ref "C407") (pin "1") (pinfunction "1_1") (pintype "passive"))
      (node (ref "R407") (pin "2") (pinfunction "2_2") (pintype "passive"))
    )
    (net (code "31") (name "Net-(U100-PH0-OSC_IN)") (class "Default")
      (node (ref "C104") (pin "1") (pinfunction "1_1") (pintype "passive"))
      (node (ref "U100") (pin "5") (pinfunction "PH0-OSC_IN_5") (pintype "bidirectional"))
      (node (ref "X101") (pin "3") (pinfunction "2_3") (pintype "passive"))
    )
    (net (code "32") (name "Net-(U100-PH1-OSC_OUT)") (class "Default")
      (node (ref "C105") (pin "1") (pinfunction "1_1") (pintype "passive"))
      (node (ref "U100") (pin "6") (pinfunction "PH1-OSC_OUT_6") (pintype "bidirectional"))
      (node (ref "X101") (pin "1") (pinfunction "1_1") (pintype "passive"))
    )
    (net (code "33") (name "Net-(U101-CANH)") (class "Default")
      (node (ref "U$2") (pin "P$25") (pinfunction "CAN_H_P$25") (pintype "bidirectional"))
      (node (ref "U$2") (pin "P$6") (pinfunction "CAN_H_P$6") (pintype "bidirectional"))
      (node (ref "U101") (pin "7") (pinfunction "CANH_7") (pintype "bidirectional"))
    )
    (net (code "34") (name "Net-(U101-CANL)") (class "Default")
      (node (ref "U$2") (pin "P$26") (pinfunction "CAN_L_P$26") (pintype "bidirectional"))
      (node (ref "U$2") (pin "P$5") (pinfunction "CAN_L_P$5") (pintype "bidirectional"))
      (node (ref "U101") (pin "6") (pinfunction "CANL_6") (pintype "bidirectional"))
    )
    (net (code "35") (name "Net-(U200-EN)") (class "Default")
      (node (ref "R201") (pin "1") (pinfunction "1_1") (pintype "passive"))
      (node (ref "R202") (pin "2") (pinfunction "2_2") (pintype "passive"))
      (node (ref "U200") (pin "1") (pinfunction "PS/SYNC_1") (pintype "input"))
      (node (ref "U200") (pin "14") (pinfunction "EN_14") (pintype "input"))
    )
    (net (code "36") (name "Net-(U200-FB)") (class "Default")
      (node (ref "R204") (pin "1") (pinfunction "1_1") (pintype "passive"))
      (node (ref "R205") (pin "2") (pinfunction "2_2") (pintype "passive"))
      (node (ref "U200") (pin "5") (pinfunction "FB_5") (pintype "passive"))
    )
    (net (code "37") (name "Net-(U200-L1)") (class "Default")
      (node (ref "L201") (pin "1") (pinfunction "1_1") (pintype "passive"))
      (node (ref "U200") (pin "11") (pinfunction "L1_11") (pintype "passive"))
    )
    (net (code "38") (name "Net-(U200-L2)") (class "Default")
      (node (ref "L201") (pin "2") (pinfunction "2_2") (pintype "passive"))
      (node (ref "U200") (pin "9") (pinfunction "L2_9") (pintype "passive"))
    )
    (net (code "39") (name "Net-(U200-VAUX)") (class "Default")
      (node (ref "C204") (pin "1") (pinfunction "1_1") (pintype "passive"))
      (node (ref "U200") (pin "3") (pinfunction "VAUX_3") (pintype "output"))
    )
    (net (code "40") (name "Net-(U200-VSEL)") (class "Default")
      (node (ref "R203") (pin "2") (pinfunction "2_2") (pintype "passive"))
      (node (ref "U200") (pin "15") (pinfunction "VSEL_15") (pintype "input"))
    )
    (net (code "41") (name "Net-(U300-OUTU)") (class "Default")
      (node (ref "JP301") (pin "1") (pinfunction "1_1") (pintype "passive"))
      (node (ref "U300") (pin "3") (pinfunction "OUTU_3") (pintype "output"))
    )
    (net (code "42") (name "Net-(U300-OUTV)") (class "Default")
      (node (ref "JP301") (pin "2") (pinfunction "2_2") (pintype "passive"))
      (node (ref "U300") (pin "8") (pinfunction "OUTV_8") (pintype "output"))
    )
    (net (code "43") (name "Net-(U300-OUTW)") (class "Default")
      (node (ref "JP301") (pin "3") (pinfunction "3_3") (pintype "passive"))
      (node (ref "U300") (pin "10") (pinfunction "OUTW_10") (pintype "output"))
    )
    (net (code "44") (name "Net-(U300-SENSEU)") (class "Default")
      (node (ref "R304") (pin "1") (pinfunction "1_1") (pintype "passive"))
      (node (ref "R305") (pin "2") (pinfunction "2_2") (pintype "passive"))
      (node (ref "R306") (pin "2") (pinfunction "2_2") (pintype "passive"))
      (node (ref "U300") (pin "4") (pinfunction "SENSEU_4") (pintype "output"))
      (node (ref "U300") (pin "9") (pinfunction "SENSEVW_9") (pintype "output"))
    )
    (net (code "45") (name "Net-(U301-IN+)") (class "Default")
      (node (ref "C308") (pin "1") (pinfunction "1_1") (pintype "passive"))
      (node (ref "R303") (pin "1") (pinfunction "1_1") (pintype "passive"))
      (node (ref "R304") (pin "2") (pinfunction "2_2") (pintype "passive"))
      (node (ref "U301") (pin "1") (pinfunction "IN+_1") (pintype "bidirectional"))
    )
    (net (code "46") (name "Net-(U301-IN-)") (class "Default")
      (node (ref "C309") (pin "2") (pinfunction "2_2") (pintype "passive"))
      (node (ref "R307") (pin "1") (pinfunction "1_1") (pintype "passive"))
      (node (ref "R308") (pin "2") (pinfunction "2_2") (pintype "passive"))
      (node (ref "U301") (pin "5") (pinfunction "IN-_5") (pintype "bidirectional"))
    )
    (net (code "47") (name "Net-(U302-MOSI)") (class "Default")
      (node (ref "R309") (pin "2") (pinfunction "2_2") (pintype "passive"))
      (node (ref "U302") (pin "4") (pinfunction "MOSI_4") (pintype "input"))
    )
    (net (code "48") (name "Net-(U400-PH)") (class "Default")
      (node (ref "R403") (pin "1") (pinfunction "1_1") (pintype "passive"))
      (node (ref "U400") (pin "1") (pinfunction "PH_1") (pintype "input"))
    )
    (net (code "49") (name "Net-(U400-PWM)") (class "Default")
      (node (ref "R404") (pin "1") (pinfunction "1_1") (pintype "passive"))
      (node (ref "U400") (pin "2") (pinfunction "PWM_2") (pintype "input"))
    )
    (net (code "50") (name "Net-(U400-REF)") (class "Default")
      (node (ref "C406") (pin "1") (pinfunction "1_1") (pintype "passive"))
      (node (ref "R405") (pin "2") (pinfunction "2_2") (pintype "passive"))
      (node (ref "R406") (pin "1") (pinfunction "1_1") (pintype "passive"))
      (node (ref "U400") (pin "11") (pinfunction "REF_11") (pintype "passive"))
    )
    (net (code "51") (name "Net-(U400-SENSEA)") (class "Default")
      (node (ref "R410") (pin "1") (pinfunction "1_1") (pintype "passive"))
      (node (ref "R411") (pin "1") (pinfunction "1_1") (pintype "passive"))
      (node (ref "R412") (pin "1") (pinfunction "1_1") (pintype "passive"))
      (node (ref "U400") (pin "4") (pinfunction "SENSEA_4") (pintype "output"))
      (node (ref "U400") (pin "9") (pinfunction "SENSEB_9") (pintype "output"))
    )
    (net (code "52") (name "Net-(U400-TOFF)") (class "Default")
      (node (ref "R407") (pin "1") (pinfunction "1_1") (pintype "passive"))
      (node (ref "R408") (pin "1") (pinfunction "1_1") (pintype "passive"))
      (node (ref "U400") (pin "12") (pinfunction "TOFF_12") (pintype "passive"))
    )
    (net (code "53") (name "Net-(U401-IN+)") (class "Default")
      (node (ref "C410") (pin "1") (pinfunction "1_1") (pintype "passive"))
      (node (ref "R409") (pin "1") (pinfunction "1_1") (pintype "passive"))
      (node (ref "R410") (pin "2") (pinfunction "2_2") (pintype "passive"))
      (node (ref "U401") (pin "1") (pinfunction "IN+_1") (pintype "bidirectional"))
    )
    (net (code "54") (name "Net-(U401-IN-)") (class "Default")
      (node (ref "C411") (pin "2") (pinfunction "2_2") (pintype "passive"))
      (node (ref "R413") (pin "1") (pinfunction "1_1") (pintype "passive"))
      (node (ref "R414") (pin "2") (pinfunction "2_2") (pintype "passive"))
      (node (ref "U401") (pin "5") (pinfunction "IN-_5") (pintype "bidirectional"))
    )
    (net (code "55") (name "OUT1") (class "Default")
      (node (ref "U$2") (pin "P$10") (pinfunction "MAG_1_P$10") (pintype "bidirectional"))
      (node (ref "U$2") (pin "P$21") (pinfunction "MAG_1_P$21") (pintype "bidirectional"))
      (node (ref "U400") (pin "10") (pinfunction "OUTB1_10") (pintype "output"))
      (node (ref "U400") (pin "3") (pinfunction "OUTA1_3") (pintype "output"))
    )
    (net (code "56") (name "OUT2") (class "Default")
      (node (ref "U$2") (pin "P$11") (pinfunction "MAG_2_P$11") (pintype "bidirectional"))
      (node (ref "U$2") (pin "P$20") (pinfunction "MAG_2_P$20") (pintype "bidirectional"))
      (node (ref "U400") (pin "5") (pinfunction "OUTA2_5") (pintype "output"))
      (node (ref "U400") (pin "8") (pinfunction "OUTB2_8") (pintype "output"))
    )
    (net (code "57") (name "SPI1_CS") (class "Default")
      (node (ref "U100") (pin "14") (pinfunction "PA4_14") (pintype "bidirectional"))
      (node (ref "U302") (pin "1") (pinfunction "CSN_1") (pintype "input"))
    )
    (net (code "58") (name "SPI1_MISO") (class "Default")
      (node (ref "U100") (pin "16") (pinfunction "PA6_16") (pintype "bidirectional"))
      (node (ref "U302") (pin "3") (pinfunction "MISO_3") (pintype "output"))
    )
    (net (code "59") (name "SPI1_SCK") (class "Default")
      (node (ref "U100") (pin "15") (pinfunction "PA5_15") (pintype "bidirectional"))
      (node (ref "U302") (pin "2") (pinfunction "SCLK_2") (pintype "input"))
    )
    (net (code "60") (name "SWCLK") (class "Default")
      (node (ref "C501") (pin "SWCLK") (pinfunction "9_SWCLK") (pintype "bidirectional"))
      (node (ref "U100") (pin "37") (pinfunction "PA14_37") (pintype "bidirectional"))
    )
    (net (code "61") (name "SWDIO") (class "Default")
      (node (ref "C501") (pin "SWDIO") (pinfunction "8_SWDIO") (pintype "bidirectional"))
      (node (ref "U100") (pin "34") (pinfunction "PA13_34") (pintype "bidirectional"))
    )
    (net (code "62") (name "UART_RX") (class "Default")
      (node (ref "C501") (pin "UART_RX") (pinfunction "5_UART_RX") (pintype "bidirectional"))
      (node (ref "U100") (pin "13") (pinfunction "PA3_13") (pintype "bidirectional"))
    )
    (net (code "63") (name "UART_TX") (class "Default")
      (node (ref "C501") (pin "UART_TX") (pinfunction "6_UART_TX") (pintype "bidirectional"))
      (node (ref "U100") (pin "12") (pinfunction "PA2_12") (pintype "bidirectional"))
    )
    (net (code "64") (name "VBUS") (class "Default")
      (node (ref "C201") (pin "1") (pinfunction "1_1") (pintype "passive"))
      (node (ref "C202") (pin "1") (pinfunction "1_1") (pintype "passive"))
      (node (ref "C203") (pin "1") (pinfunction "1_1") (pintype "passive"))
      (node (ref "C301") (pin "1") (pinfunction "1_1") (pintype "passive"))
      (node (ref "C302") (pin "1") (pinfunction "1_1") (pintype "passive"))
      (node (ref "C303") (pin "1") (pinfunction "1_1") (pintype "passive"))
      (node (ref "C401") (pin "1") (pinfunction "1_1") (pintype "passive"))
      (node (ref "C402") (pin "1") (pinfunction "1_1") (pintype "passive"))
      (node (ref "C403") (pin "1") (pinfunction "1_1") (pintype "passive"))
      (node (ref "C501") (pin "VBUS") (pinfunction "1_VBUS") (pintype "bidirectional"))
      (node (ref "R201") (pin "2") (pinfunction "2_2") (pintype "passive"))
      (node (ref "U$2") (pin "P$12") (pinfunction "VCC_P$12") (pintype "bidirectional"))
      (node (ref "U$2") (pin "P$13") (pinfunction "VCC_P$13") (pintype "bidirectional"))
      (node (ref "U$2") (pin "P$18") (pinfunction "VCC_P$18") (pintype "bidirectional"))
      (node (ref "U$2") (pin "P$19") (pinfunction "VCC_P$19") (pintype "bidirectional"))
      (node (ref "U$2") (pin "P$27") (pinfunction "VCC_P$27") (pintype "bidirectional"))
      (node (ref "U$2") (pin "P$28") (pinfunction "VCC_P$28") (pintype "bidirectional"))
      (node (ref "U$2") (pin "P$3") (pinfunction "VCC_P$3") (pintype "bidirectional"))
      (node (ref "U$2") (pin "P$4") (pinfunction "VCC_P$4") (pintype "bidirectional"))
      (node (ref "U200") (pin "12-13") (pinfunction "VIN_12-13") (pintype "power_in"))
      (node (ref "U300") (pin "6") (pinfunction "VS_6") (pintype "power_in"))
      (node (ref "U400") (pin "6") (pinfunction "VS_6") (pintype "power_in"))
    )
    (net (code "65") (name "unconnected-(U100-PC13-Pad2)") (class "Default")
      (node (ref "U100") (pin "2") (pinfunction "PC13_2") (pintype "bidirectional"))
    )
    (net (code "66") (name "unconnected-(U100-PC14-OSC32_IN-Pad3)") (class "Default")
      (node (ref "U100") (pin "3") (pinfunction "PC14-OSC32_IN_3") (pintype "bidirectional"))
    )
    (net (code "67") (name "unconnected-(U100-PC15-OSC32_OUT-Pad4)") (class "Default")
      (node (ref "U100") (pin "4") (pinfunction "PC15-OSC32_OUT_4") (pintype "bidirectional"))
    )
    (net (code "68") (name "unconnected-(U101-SHDN-Pad5)") (class "Default")
      (node (ref "U101") (pin "5") (pinfunction "SHDN_5") (pintype "input"))
    )
    (net (code "69") (name "unconnected-(U200-FB2-Pad6)") (class "Default")
      (node (ref "U200") (pin "6") (pinfunction "FB2_6") (pintype "passive"))
    )
    (net (code "70") (name "unconnected-(U200-PG-Pad2)") (class "Default")
      (node (ref "U200") (pin "2") (pinfunction "PG_2") (pintype "open_collector"))
    )
    (net (code "71") (name "unconnected-(U302-A-Pad7)") (class "Default")
      (node (ref "U302") (pin "7") (pinfunction "A_7") (pintype "output"))
    )
    (net (code "72") (name "unconnected-(U302-B-Pad6)") (class "Default")
      (node (ref "U302") (pin "6") (pinfunction "B_6") (pintype "output"))
    )
    (net (code "73") (name "unconnected-(U302-I{slash}PWM-Pad14)") (class "Default")
      (node (ref "U302") (pin "14") (pinfunction "I/PWM_14") (pintype "output"))
    )
    (net (code "74") (name "unconnected-(U302-U-Pad10)") (class "Default")
      (node (ref "U302") (pin "10") (pinfunction "U_10") (pintype "output"))
    )
    (net (code "75") (name "unconnected-(U302-V-Pad9)") (class "Default")
      (node (ref "U302") (pin "9") (pinfunction "V_9") (pintype "output"))
    )
    (net (code "76") (name "unconnected-(U302-W{slash}PWM-Pad8)") (class "Default")
      (node (ref "U302") (pin "8") (pinfunction "W/PWM_8") (pintype "output"))
    )
  )
)
